# Zio_Qwiic_Haptic_Motor_Controller_DRV260.net
KiCad netlist of a schematic drawn in EAGLE
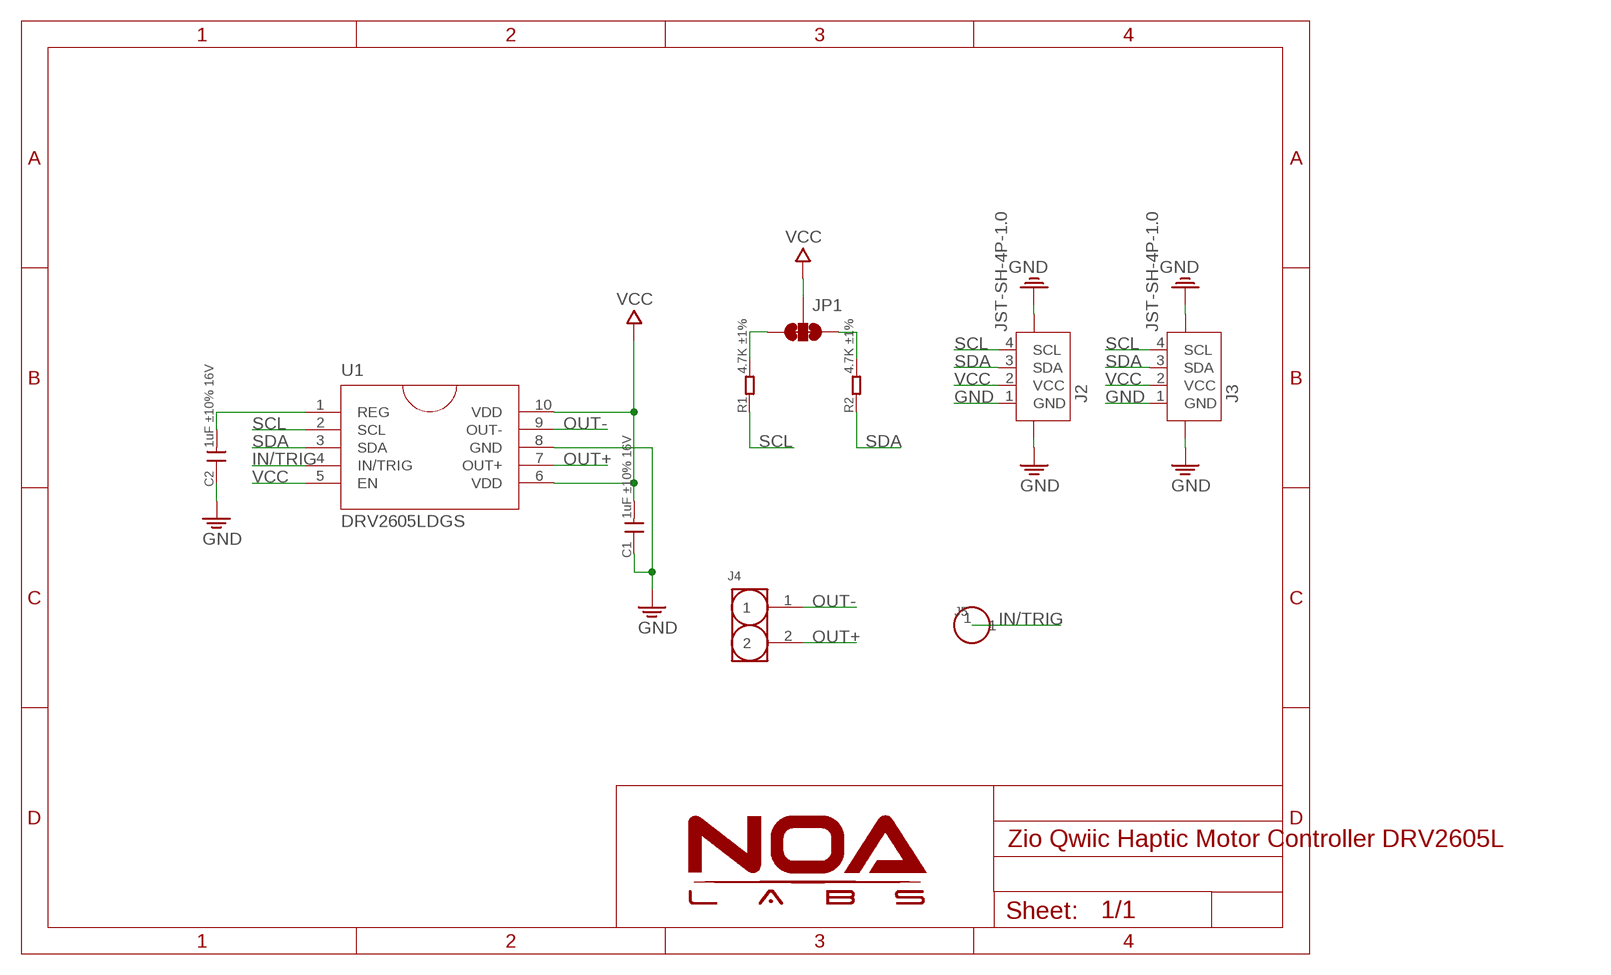
[diagram p0: schematic, sheet 1]

(export (version "E")
  (design (tool "Eeschema 10.0.6"))
  (components
    (comp (ref "C1")
      (value "1uF ±10% 16V")
      (footprint "eagle-import:C0603")
      (libsource (lib "eagle-import") (part "C-0603"))
    )
    (comp (ref "C2")
      (value "1uF ±10% 16V")
      (footprint "eagle-import:C0603")
      (libsource (lib "eagle-import") (part "C-0603"))
    )
    (comp (ref "J2")
      (value "JST-SH-4P-1.0")
      (footprint "eagle-import:JST-SH-4P")
      (libsource (lib "eagle-import") (part "JST-SH-4P-1.0"))
    )
    (comp (ref "J3")
      (value "JST-SH-4P-1.0")
      (footprint "eagle-import:JST-SH-4P")
      (libsource (lib "eagle-import") (part "JST-SH-4P-1.0"))
    )
    (comp (ref "J4")
      (value "HEADER-2P-2.0")
      (footprint "eagle-import:2P-2.0")
      (libsource (lib "eagle-import") (part "HEADER-2P-2.0"))
    )
    (comp (ref "J5")
      (value "HEADER-1P")
      (footprint "eagle-import:1P-40MIL")
      (libsource (lib "eagle-import") (part "HEADER-1P"))
    )
    (comp (ref "JP1")
      (value "SMT-JUMPER_3_2-NC_TRACE")
      (footprint "eagle-import:SMT-JUMPER_3_2-NC_TRACE")
      (libsource (lib "eagle-import") (part "SMT-JUMPER_3_2-NC_TRACE"))
    )
    (comp (ref "R1")
      (value "4.7K ±1%")
      (footprint "eagle-import:R0402")
      (libsource (lib "eagle-import") (part "R-0402"))
    )
    (comp (ref "R2")
      (value "4.7K ±1%")
      (footprint "eagle-import:R0402")
      (libsource (lib "eagle-import") (part "R-0402"))
    )
    (comp (ref "U1")
      (value "DRV2605LDGS")
      (footprint "eagle-import:VSSOP10")
      (libsource (lib "eagle-import") (part "DRV2605L"))
    )
  )
  (nets
    (net (code "1") (name "/IN{slash}TRIG") (class "Default")
      (node (ref "J5") (pin "1") (pinfunction "1_1") (pintype "bidirectional"))
      (node (ref "U1") (pin "4") (pinfunction "IN/TRIG_4") (pintype "bidirectional"))
    )
    (net (code "2") (name "/OUT+") (class "Default")
      (node (ref "J4") (pin "2") (pinfunction "2_2") (pintype "bidirectional"))
      (node (ref "U1") (pin "7") (pinfunction "OUT+_7") (pintype "bidirectional"))
    )
    (net (code "3") (name "/OUT-") (class "Default")
      (node (ref "J4") (pin "1") (pinfunction "1_1") (pintype "bidirectional"))
      (node (ref "U1") (pin "9") (pinfunction "OUT-_9") (pintype "bidirectional"))
    )
    (net (code "4") (name "/SCL") (class "Default")
      (node (ref "J2") (pin "4") (pinfunction "SCL_4") (pintype "bidirectional"))
      (node (ref "J3") (pin "4") (pinfunction "SCL_4") (pintype "bidirectional"))
      (node (ref "R1") (pin "1") (pinfunction "1_1") (pintype "passive"))
      (node (ref "U1") (pin "2") (pinfunction "SCL_2") (pintype "bidirectional"))
    )
    (net (code "5") (name "/SDA") (class "Default")
      (node (ref "J2") (pin "3") (pinfunction "SDA_3") (pintype "bidirectional"))
      (node (ref "J3") (pin "3") (pinfunction "SDA_3") (pintype "bidirectional"))
      (node (ref "R2") (pin "1") (pinfunction "1_1") (pintype "passive"))
      (node (ref "U1") (pin "3") (pinfunction "SDA_3") (pintype "bidirectional"))
    )
    (net (code "6") (name "GND") (class "Default")
      (node (ref "C1") (pin "1") (pinfunction "1_1") (pintype "passive"))
      (node (ref "C2") (pin "1") (pinfunction "1_1") (pintype "passive"))
      (node (ref "J2") (pin "1") (pinfunction "GND_1") (pintype "bidirectional"))
      (node (ref "J2") (pin "NC1") (pinfunction "5_NC1") (pintype "bidirectional"))
      (node (ref "J2") (pin "NC2") (pinfunction "6_NC2") (pintype "bidirectional"))
      (node (ref "J3") (pin "1") (pinfunction "GND_1") (pintype "bidirectional"))
      (node (ref "J3") (pin "NC1") (pinfunction "5_NC1") (pintype "bidirectional"))
      (node (ref "J3") (pin "NC2") (pinfunction "6_NC2") (pintype "bidirectional"))
      (node (ref "U1") (pin "8") (pinfunction "GND_8") (pintype "bidirectional"))
    )
    (net (code "7") (name "Net-(JP1-Pad1)") (class "Default")
      (node (ref "JP1") (pin "1") (pinfunction "1_1") (pintype "passive"))
      (node (ref "R2") (pin "2") (pinfunction "2_2") (pintype "passive"))
    )
    (net (code "8") (name "Net-(JP1-Pad3)") (class "Default")
      (node (ref "JP1") (pin "3") (pinfunction "3_3") (pintype "passive"))
      (node (ref "R1") (pin "2") (pinfunction "2_2") (pintype "passive"))
    )
    (net (code "9") (name "Net-(U1-REG)") (class "Default")
      (node (ref "C2") (pin "2") (pinfunction "2_2") (pintype "passive"))
      (node (ref "U1") (pin "1") (pinfunction "REG_1") (pintype "bidirectional"))
    )
    (net (code "10") (name "VCC") (class "Default")
      (node (ref "C1") (pin "2") (pinfunction "2_2") (pintype "passive"))
      (node (ref "J2") (pin "2") (pinfunction "VCC_2") (pintype "bidirectional"))
      (node (ref "J3") (pin "2") (pinfunction "VCC_2") (pintype "bidirectional"))
      (node (ref "JP1") (pin "2") (pinfunction "2_2") (pintype "passive"))
      (node (ref "U1") (pin "10") (pinfunction "VDD_10") (pintype "bidirectional"))
      (node (ref "U1") (pin "5") (pinfunction "EN_5") (pintype "bidirectional"))
      (node (ref "U1") (pin "6") (pinfunction "VDD_6") (pintype "bidirectional"))
    )
  )
)
